# MultimediaEthernet_MCU.net
KiCad netlist of a schematic drawn in Altium Designer
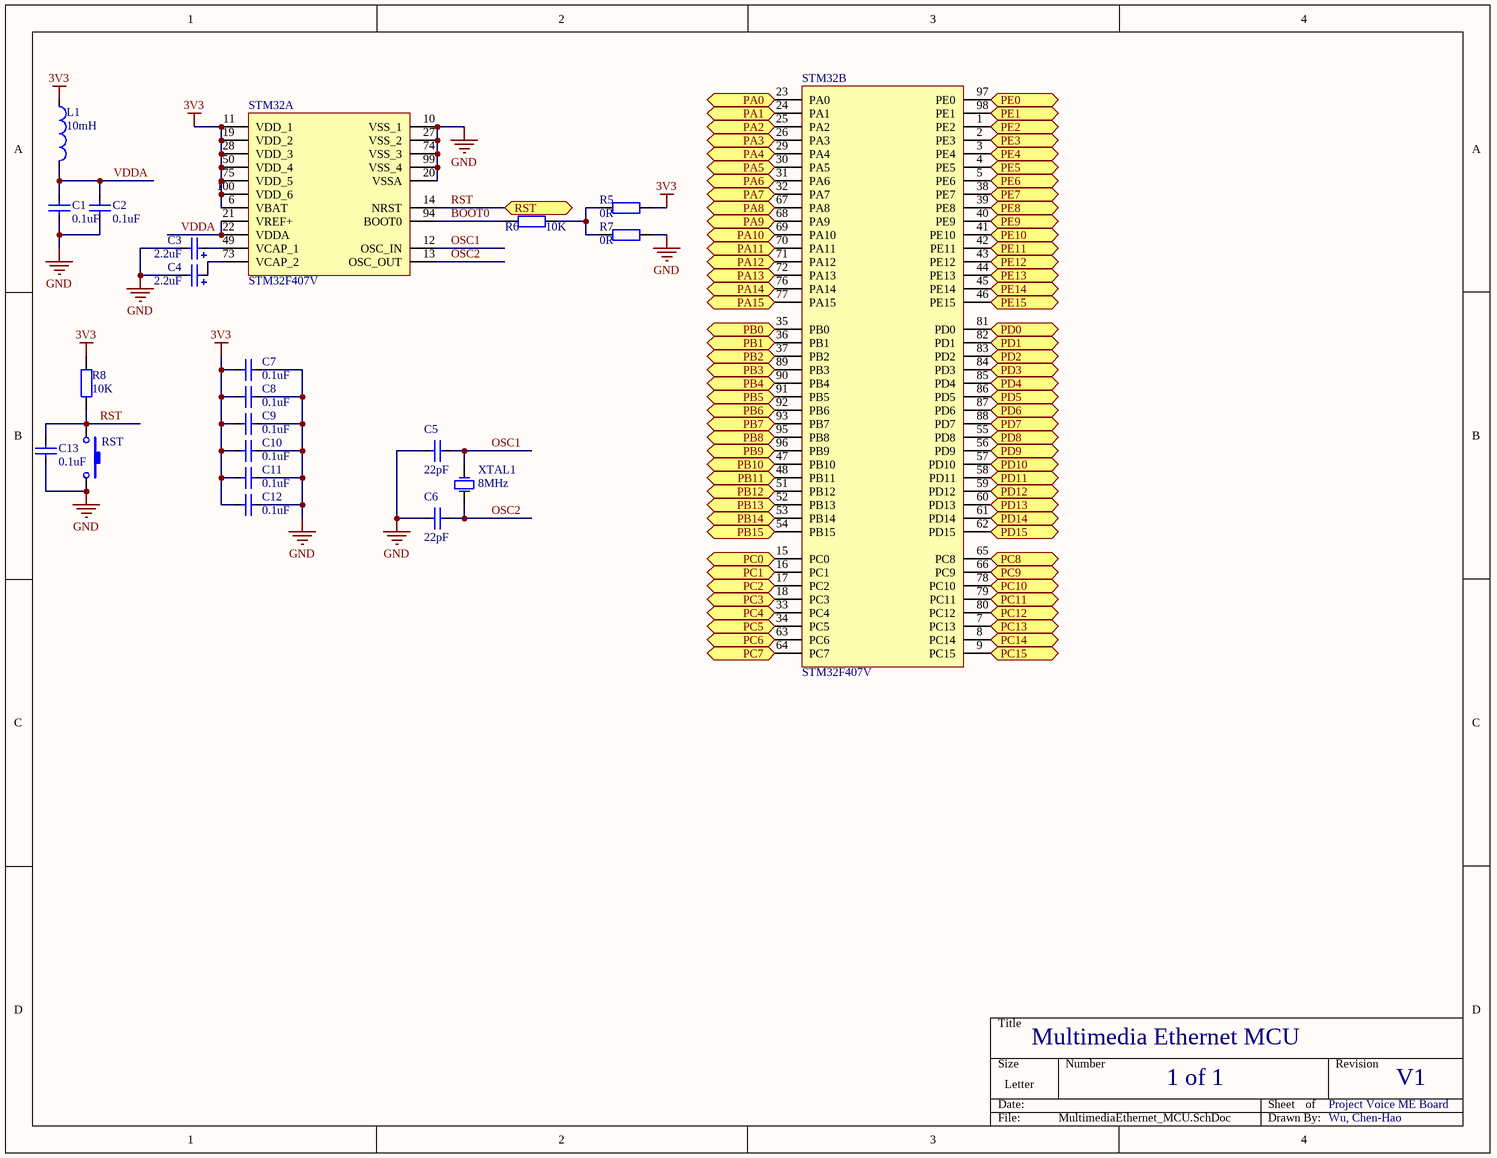
[diagram p0: MultimediaEthernet_MCU.SchDoc]

(export (version "E")
  (design (tool "Eeschema 10.0.6"))
  (components
    (comp (ref "C1")
      (value "0.1uF")
      (footprint "PCB_Passive:CAP_0603")
      (description "Capacitor")
      (fields (field (name "Comment") "Cap_0603"))
      (libsource (lib "SCH_Passive") (part "Cap_0603"))
    )
    (comp (ref "C2")
      (value "0.1uF")
      (footprint "PCB_Passive:CAP_0603")
      (description "Capacitor")
      (fields (field (name "Comment") "Cap_0603"))
      (libsource (lib "SCH_Passive") (part "Cap_0603"))
    )
    (comp (ref "C3")
      (value "2.2uF")
      (footprint "PCB_Passive:CAP_TAN_P0805")
      (description "Capacitor")
      (fields (field (name "Comment") "Cap_Tan_0805"))
      (libsource (lib "SCH_Passive") (part "Cap_Tan_0805"))
    )
    (comp (ref "C4")
      (value "2.2uF")
      (footprint "PCB_Passive:CAP_TAN_P0805")
      (description "Capacitor")
      (fields (field (name "Comment") "Cap_Tan_0805"))
      (libsource (lib "SCH_Passive") (part "Cap_Tan_0805"))
    )
    (comp (ref "C5")
      (value "22pF")
      (footprint "PCB_Passive:CAP_0603")
      (description "Capacitor")
      (fields (field (name "Comment") "Cap_0603"))
      (libsource (lib "SCH_Passive") (part "Cap_0603"))
    )
    (comp (ref "C6")
      (value "22pF")
      (footprint "PCB_Passive:CAP_0603")
      (description "Capacitor")
      (fields (field (name "Comment") "Cap_0603"))
      (libsource (lib "SCH_Passive") (part "Cap_0603"))
    )
    (comp (ref "C7")
      (value "0.1uF")
      (footprint "PCB_Passive:CAP_0603")
      (description "Capacitor")
      (fields (field (name "Comment") "Cap_0603"))
      (libsource (lib "SCH_Passive") (part "Cap_0603"))
    )
    (comp (ref "C8")
      (value "0.1uF")
      (footprint "PCB_Passive:CAP_0603")
      (description "Capacitor")
      (fields (field (name "Comment") "Cap_0603"))
      (libsource (lib "SCH_Passive") (part "Cap_0603"))
    )
    (comp (ref "C9")
      (value "0.1uF")
      (footprint "PCB_Passive:CAP_0603")
      (description "Capacitor")
      (fields (field (name "Comment") "Cap_0603"))
      (libsource (lib "SCH_Passive") (part "Cap_0603"))
    )
    (comp (ref "C10")
      (value "0.1uF")
      (footprint "PCB_Passive:CAP_0603")
      (description "Capacitor")
      (fields (field (name "Comment") "Cap_0603"))
      (libsource (lib "SCH_Passive") (part "Cap_0603"))
    )
    (comp (ref "C11")
      (value "0.1uF")
      (footprint "PCB_Passive:CAP_0603")
      (description "Capacitor")
      (fields (field (name "Comment") "Cap_0603"))
      (libsource (lib "SCH_Passive") (part "Cap_0603"))
    )
    (comp (ref "C12")
      (value "0.1uF")
      (footprint "PCB_Passive:CAP_0603")
      (description "Capacitor")
      (fields (field (name "Comment") "Cap_0603"))
      (libsource (lib "SCH_Passive") (part "Cap_0603"))
    )
    (comp (ref "C13")
      (value "0.1uF")
      (footprint "PCB_Passive:CAP_0603")
      (description "Capacitor")
      (fields (field (name "Comment") "Cap_0603"))
      (libsource (lib "SCH_Passive") (part "Cap_0603"))
    )
    (comp (ref "L1")
      (value "10mH")
      (footprint "PCB_Passive:IND_0603")
      (description "Inductor")
      (fields (field (name "Comment") "Ind_0603"))
      (libsource (lib "SCH_Passive") (part "Ind_0603"))
    )
    (comp (ref "R5")
      (value "0R")
      (footprint "PCB_Passive:RES_0603")
      (description "Resistor")
      (fields (field (name "Comment") "Res_0603"))
      (libsource (lib "") (part "Res_0603_1"))
    )
    (comp (ref "R6")
      (value "10K")
      (footprint "PCB_Passive:RES_0603")
      (description "Resistor")
      (fields (field (name "Comment") "Res_0603"))
      (libsource (lib "") (part "Res_0603_1"))
    )
    (comp (ref "R7")
      (value "0R")
      (footprint "PCB_Passive:RES_0603")
      (description "Resistor")
      (fields (field (name "Comment") "Res_0603"))
      (libsource (lib "") (part "Res_0603_1"))
    )
    (comp (ref "R8")
      (value "10K")
      (footprint "PCB_Passive:RES_0603")
      (description "Resistor")
      (fields (field (name "Comment") "Res_0603"))
      (libsource (lib "SCH_Passive") (part "Res_0603"))
    )
    (comp (ref "RST")
      (value "SW-PB_1")
      (footprint "PCB_Switch:BT_90_T")
      (description "Switch")
      (fields (field (name "PUBLISHER") "Altium Limited"))
      (libsource (lib "SCH_Switch") (part "SW-PB_1"))
    )
    (comp (ref "STM32")
      (value "STM32F407V")
      (footprint "PCB_IC:STM32F_100")
      (description "MCU")
      (libsource (lib "SCH_IC") (part "STM32F407V"))
    )
    (comp (ref "XTAL1")
      (value "8MHz")
      (footprint "PCB_Oscillator:XTAL_5032")
      (description "Crystal Oscillator")
      (fields (field (name "Comment") "XTAL_5032") (field (name "PUBLISHER") "Altium Limited"))
      (libsource (lib "SCH_Oscillator") (part "XTAL_5032"))
    )
  )
  (nets
    (net (code "1") (name "/BOOT0") (class "Default")
      (node (ref "R6") (pin "1") (pinfunction "1_1") (pintype "passive"))
      (node (ref "STM32") (pin "94") (pinfunction "BOOT0_94") (pintype "passive"))
    )
    (net (code "2") (name "/OSC1") (class "Default")
      (node (ref "C5") (pin "2") (pinfunction "2_2") (pintype "passive"))
      (node (ref "STM32") (pin "12") (pinfunction "OSC_IN_12") (pintype "passive"))
      (node (ref "XTAL1") (pin "2") (pinfunction "OSC2_2") (pintype "passive"))
    )
    (net (code "3") (name "/OSC2") (class "Default")
      (node (ref "C6") (pin "2") (pinfunction "2_2") (pintype "passive"))
      (node (ref "STM32") (pin "13") (pinfunction "OSC_OUT_13") (pintype "passive"))
      (node (ref "XTAL1") (pin "1") (pinfunction "OSC1_1") (pintype "passive"))
    )
    (net (code "4") (name "/PA0") (class "Default")
      (node (ref "STM32") (pin "23") (pinfunction "PA0_23") (pintype "passive"))
    )
    (net (code "5") (name "/PA1") (class "Default")
      (node (ref "STM32") (pin "24") (pinfunction "PA1_24") (pintype "passive"))
    )
    (net (code "6") (name "/PA2") (class "Default")
      (node (ref "STM32") (pin "25") (pinfunction "PA2_25") (pintype "passive"))
    )
    (net (code "7") (name "/PA3") (class "Default")
      (node (ref "STM32") (pin "26") (pinfunction "PA3_26") (pintype "passive"))
    )
    (net (code "8") (name "/PA4") (class "Default")
      (node (ref "STM32") (pin "29") (pinfunction "PA4_29") (pintype "passive"))
    )
    (net (code "9") (name "/PA5") (class "Default")
      (node (ref "STM32") (pin "30") (pinfunction "PA5_30") (pintype "passive"))
    )
    (net (code "10") (name "/PA6") (class "Default")
      (node (ref "STM32") (pin "31") (pinfunction "PA6_31") (pintype "passive"))
    )
    (net (code "11") (name "/PA7") (class "Default")
      (node (ref "STM32") (pin "32") (pinfunction "PA7_32") (pintype "passive"))
    )
    (net (code "12") (name "/PA8") (class "Default")
      (node (ref "STM32") (pin "67") (pinfunction "PA8_67") (pintype "passive"))
    )
    (net (code "13") (name "/PA9") (class "Default")
      (node (ref "STM32") (pin "68") (pinfunction "PA9_68") (pintype "passive"))
    )
    (net (code "14") (name "/PA10") (class "Default")
      (node (ref "STM32") (pin "69") (pinfunction "PA10_69") (pintype "passive"))
    )
    (net (code "15") (name "/PA11") (class "Default")
      (node (ref "STM32") (pin "70") (pinfunction "PA11_70") (pintype "passive"))
    )
    (net (code "16") (name "/PA12") (class "Default")
      (node (ref "STM32") (pin "71") (pinfunction "PA12_71") (pintype "passive"))
    )
    (net (code "17") (name "/PA13") (class "Default")
      (node (ref "STM32") (pin "72") (pinfunction "PA13_72") (pintype "passive"))
    )
    (net (code "18") (name "/PA14") (class "Default")
      (node (ref "STM32") (pin "76") (pinfunction "PA14_76") (pintype "passive"))
    )
    (net (code "19") (name "/PA15") (class "Default")
      (node (ref "STM32") (pin "77") (pinfunction "PA15_77") (pintype "passive"))
    )
    (net (code "20") (name "/PB0") (class "Default")
      (node (ref "STM32") (pin "35") (pinfunction "PB0_35") (pintype "passive"))
    )
    (net (code "21") (name "/PB1") (class "Default")
      (node (ref "STM32") (pin "36") (pinfunction "PB1_36") (pintype "passive"))
    )
    (net (code "22") (name "/PB2") (class "Default")
      (node (ref "STM32") (pin "37") (pinfunction "PB2_37") (pintype "passive"))
    )
    (net (code "23") (name "/PB3") (class "Default")
      (node (ref "STM32") (pin "89") (pinfunction "PB3_89") (pintype "passive"))
    )
    (net (code "24") (name "/PB4") (class "Default")
      (node (ref "STM32") (pin "90") (pinfunction "PB4_90") (pintype "passive"))
    )
    (net (code "25") (name "/PB5") (class "Default")
      (node (ref "STM32") (pin "91") (pinfunction "PB5_91") (pintype "passive"))
    )
    (net (code "26") (name "/PB6") (class "Default")
      (node (ref "STM32") (pin "92") (pinfunction "PB6_92") (pintype "passive"))
    )
    (net (code "27") (name "/PB7") (class "Default")
      (node (ref "STM32") (pin "93") (pinfunction "PB7_93") (pintype "passive"))
    )
    (net (code "28") (name "/PB8") (class "Default")
      (node (ref "STM32") (pin "95") (pinfunction "PB8_95") (pintype "passive"))
    )
    (net (code "29") (name "/PB9") (class "Default")
      (node (ref "STM32") (pin "96") (pinfunction "PB9_96") (pintype "passive"))
    )
    (net (code "30") (name "/PB10") (class "Default")
      (node (ref "STM32") (pin "47") (pinfunction "PB10_47") (pintype "passive"))
    )
    (net (code "31") (name "/PB11") (class "Default")
      (node (ref "STM32") (pin "48") (pinfunction "PB11_48") (pintype "passive"))
    )
    (net (code "32") (name "/PB12") (class "Default")
      (node (ref "STM32") (pin "51") (pinfunction "PB12_51") (pintype "passive"))
    )
    (net (code "33") (name "/PB13") (class "Default")
      (node (ref "STM32") (pin "52") (pinfunction "PB13_52") (pintype "passive"))
    )
    (net (code "34") (name "/PB14") (class "Default")
      (node (ref "STM32") (pin "53") (pinfunction "PB14_53") (pintype "passive"))
    )
    (net (code "35") (name "/PB15") (class "Default")
      (node (ref "STM32") (pin "54") (pinfunction "PB15_54") (pintype "passive"))
    )
    (net (code "36") (name "/PC0") (class "Default")
      (node (ref "STM32") (pin "15") (pinfunction "PC0_15") (pintype "passive"))
    )
    (net (code "37") (name "/PC1") (class "Default")
      (node (ref "STM32") (pin "16") (pinfunction "PC1_16") (pintype "passive"))
    )
    (net (code "38") (name "/PC2") (class "Default")
      (node (ref "STM32") (pin "17") (pinfunction "PC2_17") (pintype "passive"))
    )
    (net (code "39") (name "/PC3") (class "Default")
      (node (ref "STM32") (pin "18") (pinfunction "PC3_18") (pintype "passive"))
    )
    (net (code "40") (name "/PC4") (class "Default")
      (node (ref "STM32") (pin "33") (pinfunction "PC4_33") (pintype "passive"))
    )
    (net (code "41") (name "/PC5") (class "Default")
      (node (ref "STM32") (pin "34") (pinfunction "PC5_34") (pintype "passive"))
    )
    (net (code "42") (name "/PC6") (class "Default")
      (node (ref "STM32") (pin "63") (pinfunction "PC6_63") (pintype "passive"))
    )
    (net (code "43") (name "/PC7") (class "Default")
      (node (ref "STM32") (pin "64") (pinfunction "PC7_64") (pintype "passive"))
    )
    (net (code "44") (name "/PC8") (class "Default")
      (node (ref "STM32") (pin "65") (pinfunction "PC8_65") (pintype "passive"))
    )
    (net (code "45") (name "/PC9") (class "Default")
      (node (ref "STM32") (pin "66") (pinfunction "PC9_66") (pintype "passive"))
    )
    (net (code "46") (name "/PC10") (class "Default")
      (node (ref "STM32") (pin "78") (pinfunction "PC10_78") (pintype "passive"))
    )
    (net (code "47") (name "/PC11") (class "Default")
      (node (ref "STM32") (pin "79") (pinfunction "PC11_79") (pintype "passive"))
    )
    (net (code "48") (name "/PC12") (class "Default")
      (node (ref "STM32") (pin "80") (pinfunction "PC12_80") (pintype "passive"))
    )
    (net (code "49") (name "/PC13") (class "Default")
      (node (ref "STM32") (pin "7") (pinfunction "PC13_7") (pintype "passive"))
    )
    (net (code "50") (name "/PC14") (class "Default")
      (node (ref "STM32") (pin "8") (pinfunction "PC14_8") (pintype "passive"))
    )
    (net (code "51") (name "/PC15") (class "Default")
      (node (ref "STM32") (pin "9") (pinfunction "PC15_9") (pintype "passive"))
    )
    (net (code "52") (name "/PD0") (class "Default")
      (node (ref "STM32") (pin "81") (pinfunction "PD0_81") (pintype "passive"))
    )
    (net (code "53") (name "/PD1") (class "Default")
      (node (ref "STM32") (pin "82") (pinfunction "PD1_82") (pintype "passive"))
    )
    (net (code "54") (name "/PD2") (class "Default")
      (node (ref "STM32") (pin "83") (pinfunction "PD2_83") (pintype "passive"))
    )
    (net (code "55") (name "/PD3") (class "Default")
      (node (ref "STM32") (pin "84") (pinfunction "PD3_84") (pintype "passive"))
    )
    (net (code "56") (name "/PD4") (class "Default")
      (node (ref "STM32") (pin "85") (pinfunction "PD4_85") (pintype "passive"))
    )
    (net (code "57") (name "/PD5") (class "Default")
      (node (ref "STM32") (pin "86") (pinfunction "PD5_86") (pintype "passive"))
    )
    (net (code "58") (name "/PD6") (class "Default")
      (node (ref "STM32") (pin "87") (pinfunction "PD6_87") (pintype "passive"))
    )
    (net (code "59") (name "/PD7") (class "Default")
      (node (ref "STM32") (pin "88") (pinfunction "PD7_88") (pintype "passive"))
    )
    (net (code "60") (name "/PD8") (class "Default")
      (node (ref "STM32") (pin "55") (pinfunction "PD8_55") (pintype "passive"))
    )
    (net (code "61") (name "/PD9") (class "Default")
      (node (ref "STM32") (pin "56") (pinfunction "PD9_56") (pintype "passive"))
    )
    (net (code "62") (name "/PD10") (class "Default")
      (node (ref "STM32") (pin "57") (pinfunction "PD10_57") (pintype "passive"))
    )
    (net (code "63") (name "/PD11") (class "Default")
      (node (ref "STM32") (pin "58") (pinfunction "PD11_58") (pintype "passive"))
    )
    (net (code "64") (name "/PD12") (class "Default")
      (node (ref "STM32") (pin "59") (pinfunction "PD12_59") (pintype "passive"))
    )
    (net (code "65") (name "/PD13") (class "Default")
      (node (ref "STM32") (pin "60") (pinfunction "PD13_60") (pintype "passive"))
    )
    (net (code "66") (name "/PD14") (class "Default")
      (node (ref "STM32") (pin "61") (pinfunction "PD14_61") (pintype "passive"))
    )
    (net (code "67") (name "/PD15") (class "Default")
      (node (ref "STM32") (pin "62") (pinfunction "PD15_62") (pintype "passive"))
    )
    (net (code "68") (name "/PE0") (class "Default")
      (node (ref "STM32") (pin "97") (pinfunction "PE0_97") (pintype "passive"))
    )
    (net (code "69") (name "/PE1") (class "Default")
      (node (ref "STM32") (pin "98") (pinfunction "PE1_98") (pintype "passive"))
    )
    (net (code "70") (name "/PE2") (class "Default")
      (node (ref "STM32") (pin "1") (pinfunction "PE2_1") (pintype "passive"))
    )
    (net (code "71") (name "/PE3") (class "Default")
      (node (ref "STM32") (pin "2") (pinfunction "PE3_2") (pintype "passive"))
    )
    (net (code "72") (name "/PE4") (class "Default")
      (node (ref "STM32") (pin "3") (pinfunction "PE4_3") (pintype "passive"))
    )
    (net (code "73") (name "/PE5") (class "Default")
      (node (ref "STM32") (pin "4") (pinfunction "PE5_4") (pintype "passive"))
    )
    (net (code "74") (name "/PE6") (class "Default")
      (node (ref "STM32") (pin "5") (pinfunction "PE6_5") (pintype "passive"))
    )
    (net (code "75") (name "/PE7") (class "Default")
      (node (ref "STM32") (pin "38") (pinfunction "PE7_38") (pintype "passive"))
    )
    (net (code "76") (name "/PE8") (class "Default")
      (node (ref "STM32") (pin "39") (pinfunction "PE8_39") (pintype "passive"))
    )
    (net (code "77") (name "/PE9") (class "Default")
      (node (ref "STM32") (pin "40") (pinfunction "PE9_40") (pintype "passive"))
    )
    (net (code "78") (name "/PE10") (class "Default")
      (node (ref "STM32") (pin "41") (pinfunction "PE10_41") (pintype "passive"))
    )
    (net (code "79") (name "/PE11") (class "Default")
      (node (ref "STM32") (pin "42") (pinfunction "PE11_42") (pintype "passive"))
    )
    (net (code "80") (name "/PE12") (class "Default")
      (node (ref "STM32") (pin "43") (pinfunction "PE12_43") (pintype "passive"))
    )
    (net (code "81") (name "/PE13") (class "Default")
      (node (ref "STM32") (pin "44") (pinfunction "PE13_44") (pintype "passive"))
    )
    (net (code "82") (name "/PE14") (class "Default")
      (node (ref "STM32") (pin "45") (pinfunction "PE14_45") (pintype "passive"))
    )
    (net (code "83") (name "/PE15") (class "Default")
      (node (ref "STM32") (pin "46") (pinfunction "PE15_46") (pintype "passive"))
    )
    (net (code "84") (name "/RST") (class "Default")
      (node (ref "C13") (pin "1") (pinfunction "1_1") (pintype "passive"))
      (node (ref "R8") (pin "2") (pinfunction "2_2") (pintype "passive"))
      (node (ref "RST") (pin "1") (pinfunction "1_1") (pintype "passive"))
      (node (ref "STM32") (pin "14") (pinfunction "NRST_14") (pintype "passive"))
    )
    (net (code "85") (name "/VDDA") (class "Default")
      (node (ref "C1") (pin "1") (pinfunction "1_1") (pintype "passive"))
      (node (ref "C2") (pin "1") (pinfunction "1_1") (pintype "passive"))
      (node (ref "L1") (pin "2") (pinfunction "2_2") (pintype "passive"))
      (node (ref "STM32") (pin "21") (pinfunction "VREF+_21") (pintype "passive"))
      (node (ref "STM32") (pin "22") (pinfunction "VDDA_22") (pintype "passive"))
    )
    (net (code "86") (name "3V3") (class "Default")
      (node (ref "C10") (pin "2") (pinfunction "2_2") (pintype "passive"))
      (node (ref "C11") (pin "2") (pinfunction "2_2") (pintype "passive"))
      (node (ref "C12") (pin "2") (pinfunction "2_2") (pintype "passive"))
      (node (ref "C7") (pin "2") (pinfunction "2_2") (pintype "passive"))
      (node (ref "C8") (pin "2") (pinfunction "2_2") (pintype "passive"))
      (node (ref "C9") (pin "2") (pinfunction "2_2") (pintype "passive"))
      (node (ref "L1") (pin "1") (pinfunction "1_1") (pintype "passive"))
      (node (ref "R5") (pin "2") (pinfunction "2_2") (pintype "passive"))
      (node (ref "R8") (pin "1") (pinfunction "1_1") (pintype "passive"))
      (node (ref "STM32") (pin "100") (pinfunction "VDD_6_100") (pintype "passive"))
      (node (ref "STM32") (pin "11") (pinfunction "VDD_1_11") (pintype "passive"))
      (node (ref "STM32") (pin "19") (pinfunction "VDD_2_19") (pintype "passive"))
      (node (ref "STM32") (pin "28") (pinfunction "VDD_3_28") (pintype "passive"))
      (node (ref "STM32") (pin "50") (pinfunction "VDD_4_50") (pintype "passive"))
      (node (ref "STM32") (pin "6") (pinfunction "VBAT_6") (pintype "passive"))
      (node (ref "STM32") (pin "75") (pinfunction "VDD_5_75") (pintype "passive"))
    )
    (net (code "87") (name "GND") (class "Default")
      (node (ref "C1") (pin "2") (pinfunction "2_2") (pintype "passive"))
      (node (ref "C10") (pin "1") (pinfunction "1_1") (pintype "passive"))
      (node (ref "C11") (pin "1") (pinfunction "1_1") (pintype "passive"))
      (node (ref "C12") (pin "1") (pinfunction "1_1") (pintype "passive"))
      (node (ref "C13") (pin "2") (pinfunction "2_2") (pintype "passive"))
      (node (ref "C2") (pin "2") (pinfunction "2_2") (pintype "passive"))
      (node (ref "C3") (pin "2") (pinfunction "2_2") (pintype "passive"))
      (node (ref "C4") (pin "2") (pinfunction "2_2") (pintype "passive"))
      (node (ref "C5") (pin "1") (pinfunction "1_1") (pintype "passive"))
      (node (ref "C6") (pin "1") (pinfunction "1_1") (pintype "passive"))
      (node (ref "C7") (pin "1") (pinfunction "1_1") (pintype "passive"))
      (node (ref "C8") (pin "1") (pinfunction "1_1") (pintype "passive"))
      (node (ref "C9") (pin "1") (pinfunction "1_1") (pintype "passive"))
      (node (ref "R7") (pin "2") (pinfunction "2_2") (pintype "passive"))
      (node (ref "RST") (pin "2") (pinfunction "2_2") (pintype "passive"))
      (node (ref "STM32") (pin "10") (pinfunction "VSS_1_10") (pintype "passive"))
      (node (ref "STM32") (pin "20") (pinfunction "VSSA_20") (pintype "passive"))
      (node (ref "STM32") (pin "27") (pinfunction "VSS_2_27") (pintype "passive"))
      (node (ref "STM32") (pin "74") (pinfunction "VSS_3_74") (pintype "passive"))
      (node (ref "STM32") (pin "99") (pinfunction "VSS_4_99") (pintype "passive"))
    )
    (net (code "88") (name "Net-(R5-Pad1)") (class "Default")
      (node (ref "R5") (pin "1") (pinfunction "1_1") (pintype "passive"))
      (node (ref "R6") (pin "2") (pinfunction "2_2") (pintype "passive"))
      (node (ref "R7") (pin "1") (pinfunction "1_1") (pintype "passive"))
    )
    (net (code "89") (name "Net-(STM32A-VCAP_1)") (class "Default")
      (node (ref "C3") (pin "1") (pinfunction "1_1") (pintype "passive"))
      (node (ref "STM32") (pin "49") (pinfunction "VCAP_1_49") (pintype "passive"))
    )
    (net (code "90") (name "Net-(STM32A-VCAP_2)") (class "Default")
      (node (ref "C4") (pin "1") (pinfunction "1_1") (pintype "passive"))
      (node (ref "STM32") (pin "73") (pinfunction "VCAP_2_73") (pintype "passive"))
    )
  )
)
